# Qwiic_ATECC608A.net
KiCad netlist of a schematic drawn in EAGLE
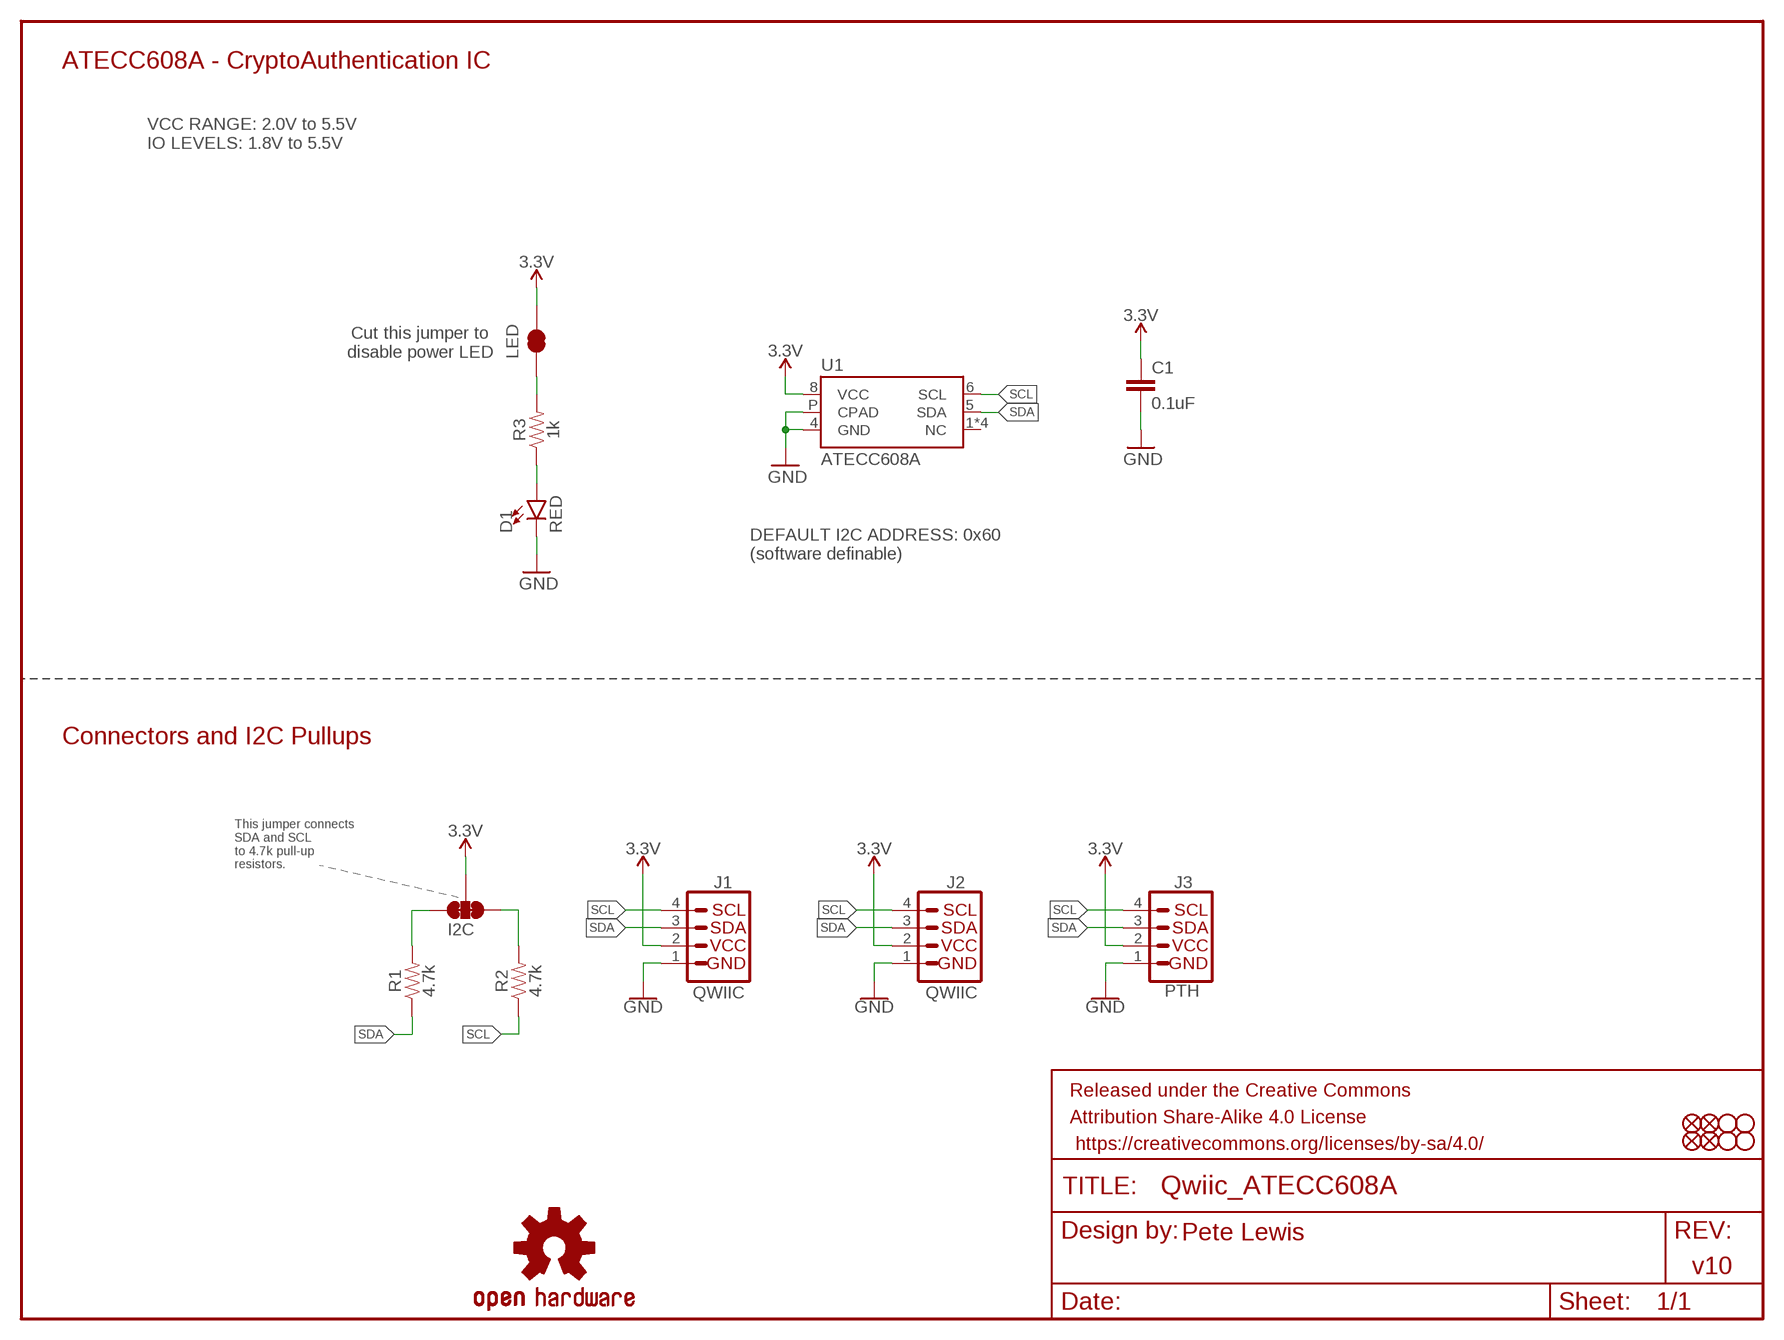
[diagram p0: schematic, sheet 1]

(export (version "E")
  (design (tool "Eeschema 10.0.6"))
  (components
    (comp (ref "C1")
      (value "0.1uF")
      (footprint "eagle-import:0603")
      (libsource (lib "eagle-import") (part "0.1UF-0603-25V-(+80/-20%)"))
    )
    (comp (ref "D1")
      (value "RED")
      (footprint "eagle-import:LED-0603")
      (libsource (lib "eagle-import") (part "LED-RED0603"))
    )
    (comp (ref "FD1")
      (value "FIDUCIAL1X2")
      (footprint "eagle-import:FIDUCIAL-1X2")
      (libsource (lib "eagle-import") (part "FIDUCIAL1X2"))
    )
    (comp (ref "FD2")
      (value "FIDUCIAL1X2")
      (footprint "eagle-import:FIDUCIAL-1X2")
      (libsource (lib "eagle-import") (part "FIDUCIAL1X2"))
    )
    (comp (ref "FD3")
      (value "FIDUCIAL1X2")
      (footprint "eagle-import:FIDUCIAL-1X2")
      (libsource (lib "eagle-import") (part "FIDUCIAL1X2"))
    )
    (comp (ref "FD4")
      (value "FIDUCIAL1X2")
      (footprint "eagle-import:FIDUCIAL-1X2")
      (libsource (lib "eagle-import") (part "FIDUCIAL1X2"))
    )
    (comp (ref "FRAME1")
      (value "FRAME-LETTER")
      (footprint "eagle-import:CREATIVE_COMMONS")
      (libsource (lib "eagle-import") (part "FRAME-LETTER"))
    )
    (comp (ref "H1")
      (value "STAND-OFF")
      (footprint "eagle-import:STAND-OFF")
      (libsource (lib "eagle-import") (part "STAND-OFF"))
    )
    (comp (ref "H2")
      (value "STAND-OFF")
      (footprint "eagle-import:STAND-OFF")
      (libsource (lib "eagle-import") (part "STAND-OFF"))
    )
    (comp (ref "H3")
      (value "STAND-OFF")
      (footprint "eagle-import:STAND-OFF")
      (libsource (lib "eagle-import") (part "STAND-OFF"))
    )
    (comp (ref "H4")
      (value "STAND-OFF")
      (footprint "eagle-import:STAND-OFF")
      (libsource (lib "eagle-import") (part "STAND-OFF"))
    )
    (comp (ref "I2C")
      (value "JUMPER-SMT_3_2-NC_TRACE_SILK")
      (footprint "eagle-import:SMT-JUMPER_3_2-NC_TRACE_SILK")
      (libsource (lib "eagle-import") (part "JUMPER-SMT_3_2-NC_TRACE_SILK"))
    )
    (comp (ref "J1")
      (value "QWIIC")
      (footprint "eagle-import:JST04_1MM_RA")
      (libsource (lib "eagle-import") (part "I2C_STANDARDQWIIC"))
    )
    (comp (ref "J2")
      (value "QWIIC")
      (footprint "eagle-import:JST04_1MM_RA")
      (libsource (lib "eagle-import") (part "I2C_STANDARDQWIIC"))
    )
    (comp (ref "J3")
      (value "PTH")
      (footprint "eagle-import:1X04_NO_SILK")
      (libsource (lib "eagle-import") (part "I2C_STANDARD_NO_SILK"))
    )
    (comp (ref "LED")
      (value "JUMPER-SMT_2_NC_TRACE_SILK")
      (footprint "eagle-import:SMT-JUMPER_2_NC_TRACE_SILK")
      (libsource (lib "eagle-import") (part "JUMPER-SMT_2_NC_TRACE_SILK"))
    )
    (comp (ref "LOGO4")
      (value "OSHW-LOGOS")
      (footprint "eagle-import:OSHW-LOGO-S")
      (libsource (lib "eagle-import") (part "OSHW-LOGOS"))
    )
    (comp (ref "R1")
      (value "4.7k")
      (footprint "eagle-import:0603")
      (libsource (lib "eagle-import") (part "4.7KOHM-0603-1/10W-1%"))
    )
    (comp (ref "R2")
      (value "4.7k")
      (footprint "eagle-import:0603")
      (libsource (lib "eagle-import") (part "4.7KOHM-0603-1/10W-1%"))
    )
    (comp (ref "R3")
      (value "1k")
      (footprint "eagle-import:0603")
      (libsource (lib "eagle-import") (part "1KOHM-0603-1/10W-1%"))
    )
    (comp (ref "U1")
      (value "ATECC608A")
      (footprint "eagle-import:UDFN_2X3MM")
      (libsource (lib "eagle-import") (part "ATECC608AUDFN_2X3MM"))
    )
  )
  (nets
    (net (code "1") (name "3.3V") (class "Default")
      (node (ref "C1") (pin "1") (pinfunction "1_1") (pintype "passive"))
      (node (ref "I2C") (pin "2") (pinfunction "2_2") (pintype "passive"))
      (node (ref "J1") (pin "2") (pinfunction "2_2") (pintype "power_in"))
      (node (ref "J2") (pin "2") (pinfunction "2_2") (pintype "power_in"))
      (node (ref "J3") (pin "2") (pinfunction "2_2") (pintype "power_in"))
      (node (ref "LED") (pin "2") (pinfunction "2_2") (pintype "passive"))
      (node (ref "U1") (pin "8") (pinfunction "VCC_8") (pintype "power_in"))
    )
    (net (code "2") (name "GND") (class "Default")
      (node (ref "C1") (pin "2") (pinfunction "2_2") (pintype "passive"))
      (node (ref "D1") (pin "C") (pinfunction "C_C") (pintype "passive"))
      (node (ref "J1") (pin "1") (pinfunction "1_1") (pintype "power_in"))
      (node (ref "J2") (pin "1") (pinfunction "1_1") (pintype "power_in"))
      (node (ref "J3") (pin "1") (pinfunction "1_1") (pintype "power_in"))
      (node (ref "U1") (pin "4") (pinfunction "GND_4") (pintype "power_in"))
      (node (ref "U1") (pin "P") (pinfunction "CPAD_P") (pintype "power_in"))
    )
    (net (code "3") (name "Net-(D1-PadA)") (class "Default")
      (node (ref "D1") (pin "A") (pinfunction "A_A") (pintype "passive"))
      (node (ref "R3") (pin "1") (pinfunction "1_1") (pintype "passive"))
    )
    (net (code "4") (name "Net-(I2C-Pad1)") (class "Default")
      (node (ref "I2C") (pin "1") (pinfunction "1_1") (pintype "passive"))
      (node (ref "R2") (pin "2") (pinfunction "2_2") (pintype "passive"))
    )
    (net (code "5") (name "Net-(I2C-Pad3)") (class "Default")
      (node (ref "I2C") (pin "3") (pinfunction "3_3") (pintype "passive"))
      (node (ref "R1") (pin "2") (pinfunction "2_2") (pintype "passive"))
    )
    (net (code "6") (name "Net-(LED-Pad1)") (class "Default")
      (node (ref "LED") (pin "1") (pinfunction "1_1") (pintype "passive"))
      (node (ref "R3") (pin "2") (pinfunction "2_2") (pintype "passive"))
    )
    (net (code "7") (name "SCL") (class "Default")
      (node (ref "J1") (pin "4") (pinfunction "4_4") (pintype "passive"))
      (node (ref "J2") (pin "4") (pinfunction "4_4") (pintype "passive"))
      (node (ref "J3") (pin "4") (pinfunction "4_4") (pintype "passive"))
      (node (ref "R2") (pin "1") (pinfunction "1_1") (pintype "passive"))
      (node (ref "U1") (pin "6") (pinfunction "SCL_6") (pintype "bidirectional"))
    )
    (net (code "8") (name "SDA") (class "Default")
      (node (ref "J1") (pin "3") (pinfunction "3_3") (pintype "passive"))
      (node (ref "J2") (pin "3") (pinfunction "3_3") (pintype "passive"))
      (node (ref "J3") (pin "3") (pinfunction "3_3") (pintype "passive"))
      (node (ref "R1") (pin "1") (pinfunction "1_1") (pintype "passive"))
      (node (ref "U1") (pin "5") (pinfunction "SDA_5") (pintype "bidirectional"))
    )
    (net (code "9") (name "unconnected-(U1-NC-Pad1)") (class "Default")
      (node (ref "U1") (pin "1") (pinfunction "NC_1") (pintype "no_connect"))
    )
    (net (code "10") (name "unconnected-(U1-NC-Pad2)") (class "Default")
      (node (ref "U1") (pin "2") (pinfunction "NC_2") (pintype "no_connect"))
    )
    (net (code "11") (name "unconnected-(U1-NC-Pad3)") (class "Default")
      (node (ref "U1") (pin "3") (pinfunction "NC_3") (pintype "no_connect"))
    )
    (net (code "12") (name "unconnected-(U1-NC-Pad7)") (class "Default")
      (node (ref "U1") (pin "7") (pinfunction "NC_7") (pintype "no_connect"))
    )
  )
)
